# nzxt-gamma-usb3.net
KiCad netlist of a schematic drawn in EAGLE
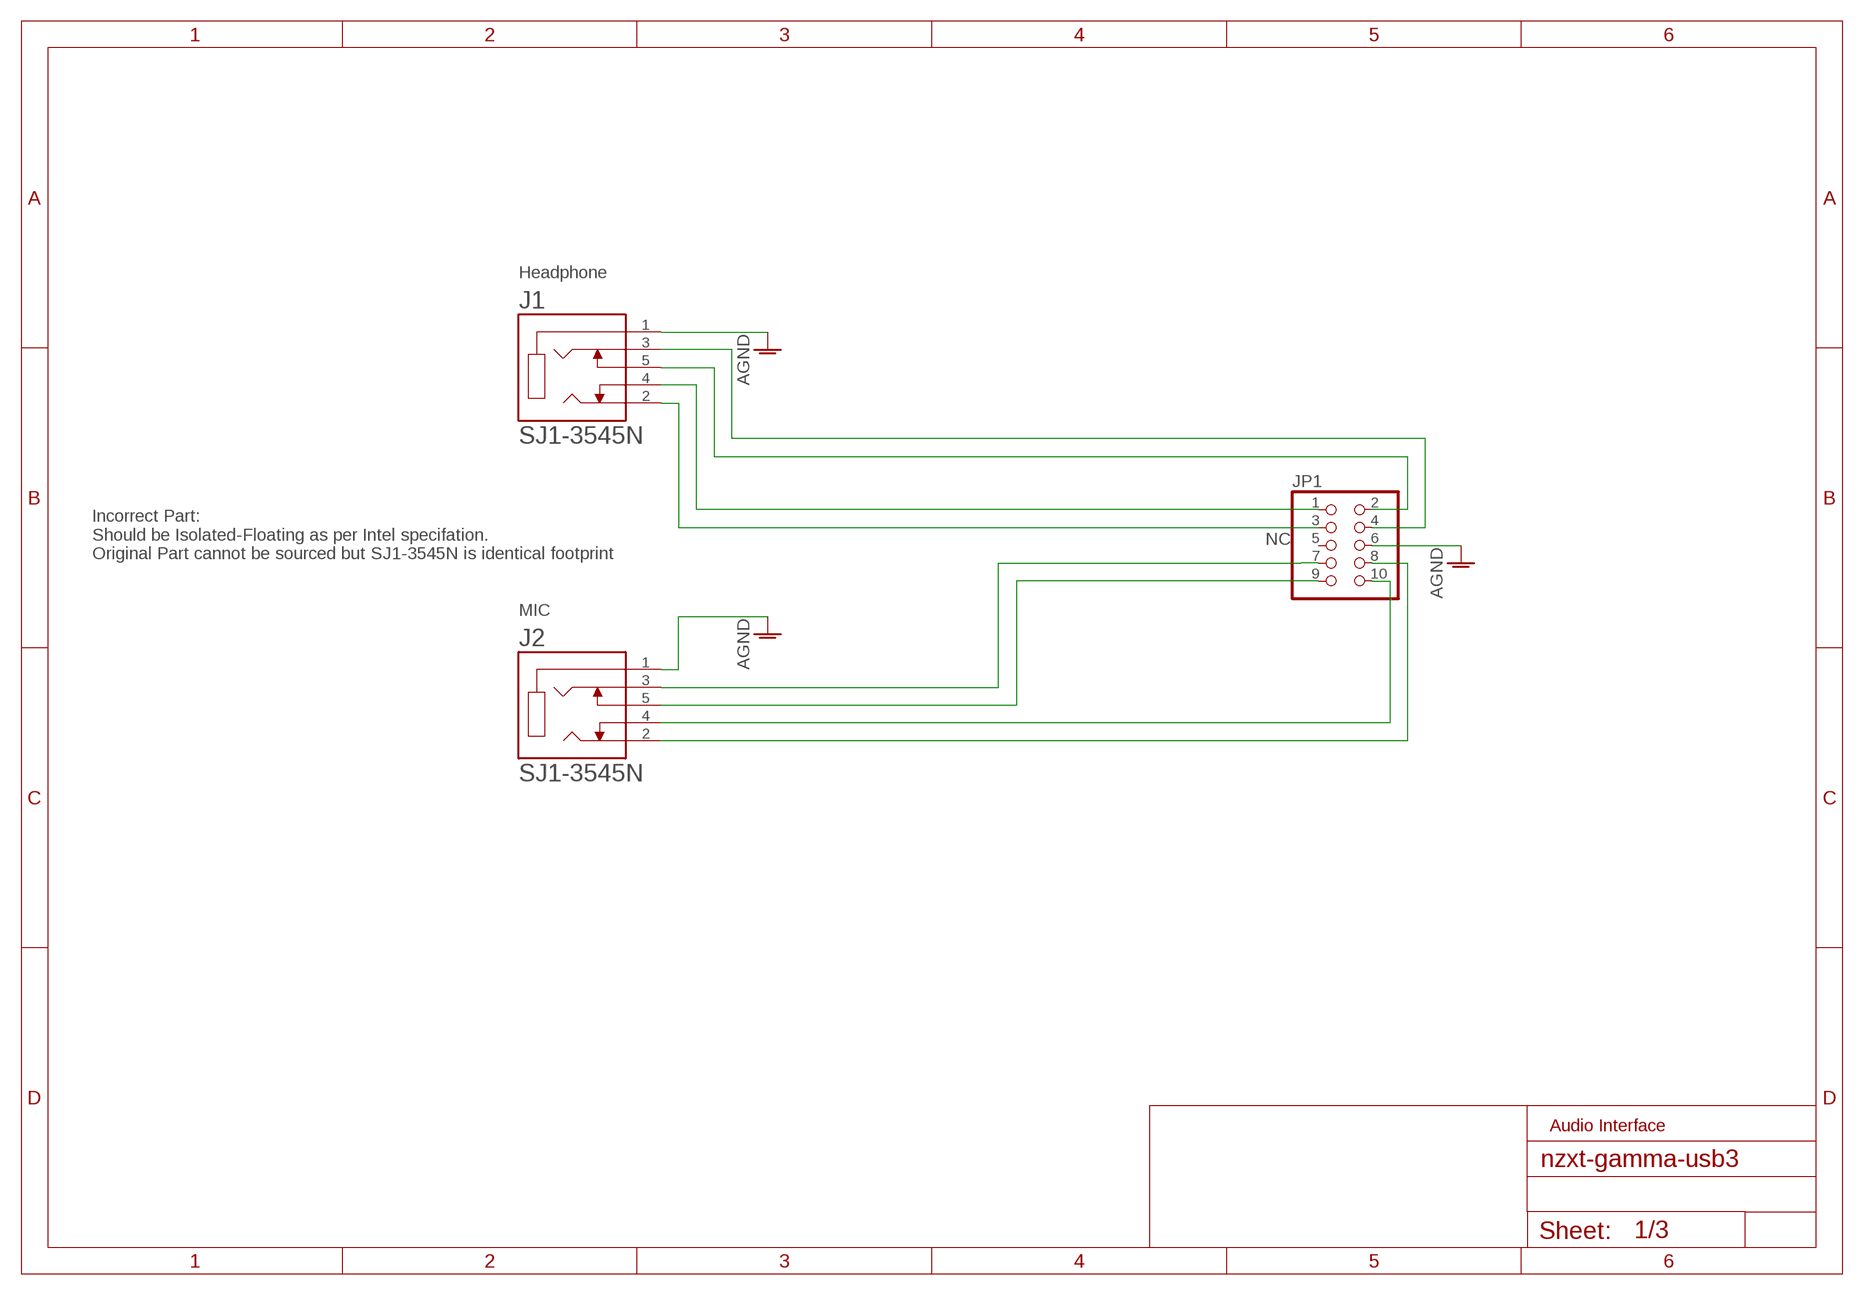
[diagram p0: schematic, sheet 1]
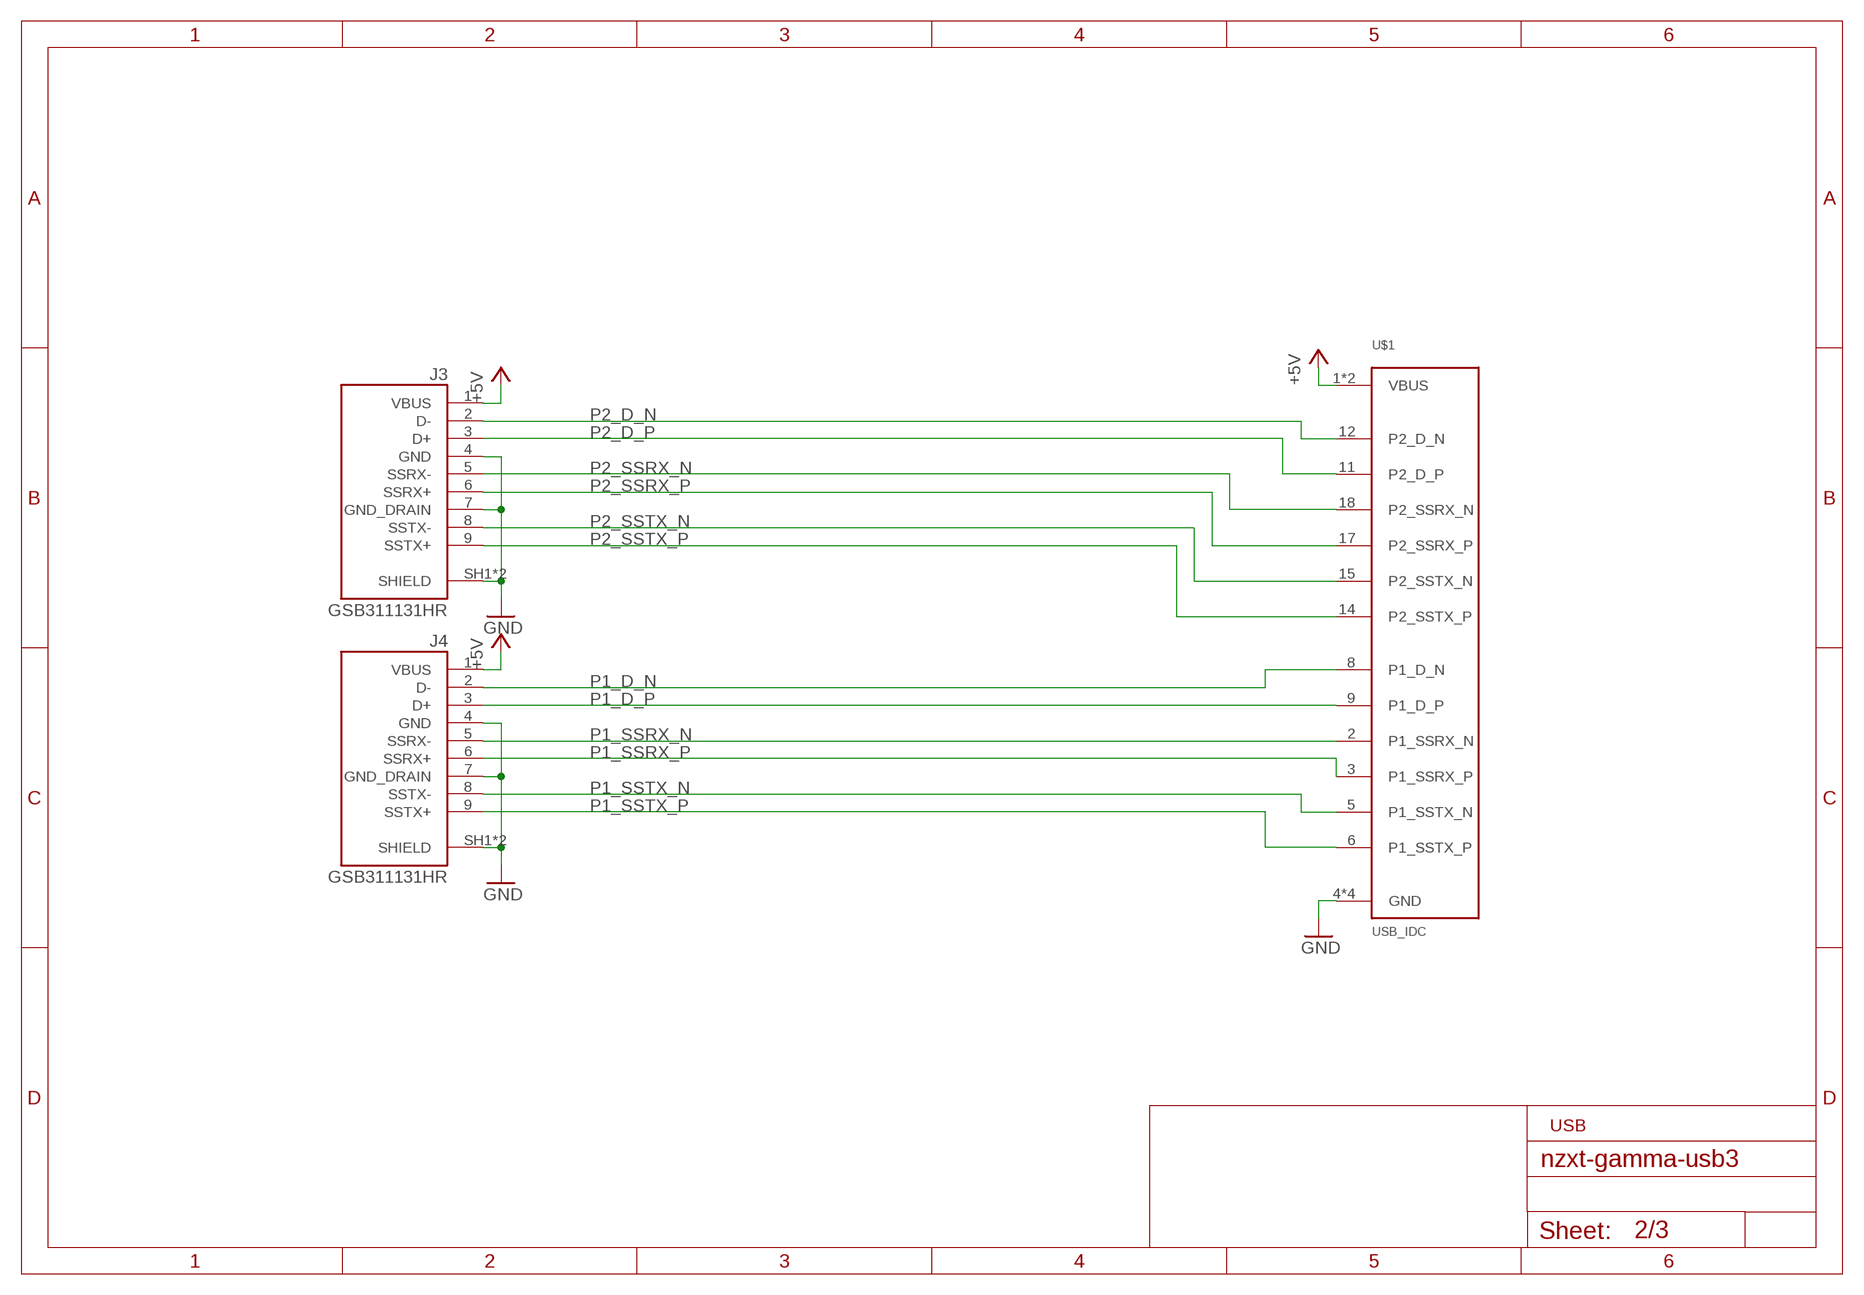
[diagram p1: schematic, sheet 2]
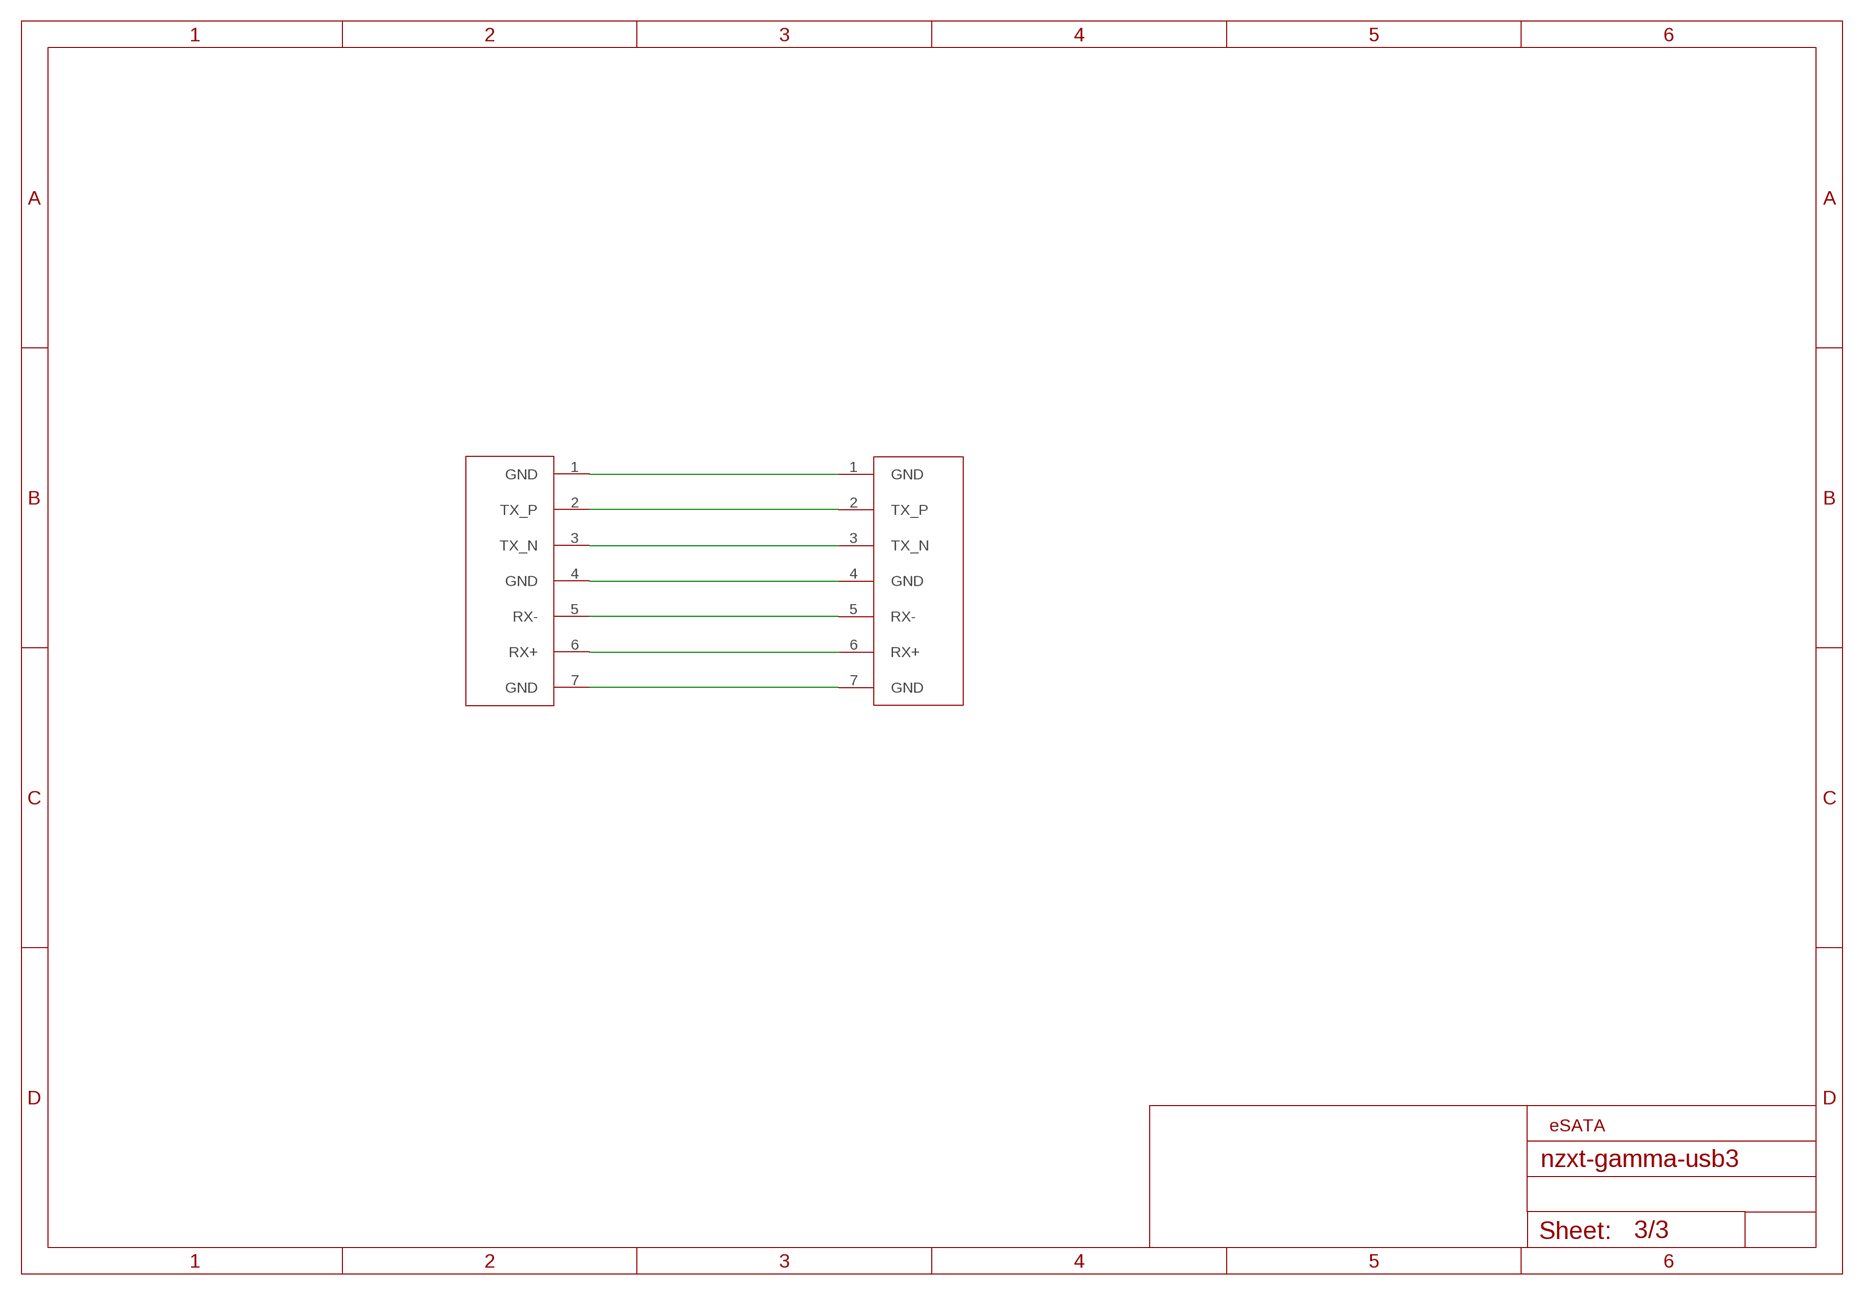
[diagram p2: schematic, sheet 3]

(export (version "E")
  (design (tool "Eeschema 10.0.6"))
  (components
    (comp (ref "J3")
      (value "GSB311131HR")
      (footprint "eagle-import:AMPHENOL_GSB311131HR")
      (fields (field (name "MF") "Amphenol Commercial"))
      (libsource (lib "eagle-import") (part "GSB311131HR"))
    )
    (comp (ref "J4")
      (value "GSB311131HR")
      (footprint "eagle-import:AMPHENOL_GSB311131HR")
      (fields (field (name "MF") "Amphenol Commercial"))
      (libsource (lib "eagle-import") (part "GSB311131HR"))
    )
    (comp (ref "U$1")
      (value "USB_IDC")
      (footprint "eagle-import:USB3_IDC")
      (libsource (lib "eagle-import") (part "USB_IDC"))
    )
    (comp (ref "U$2")
      (value "G091208300LF")
      (footprint "eagle-import:G091208300LF")
      (libsource (lib "eagle-import") (part "G091208300LF"))
    )
    (comp (ref "U$3")
      (value "0678007001")
      (footprint "eagle-import:0678007001")
      (fields (field (name "MF") "Molex"))
      (libsource (lib "eagle-import") (part "0678007001"))
    )
    (comp (ref "J1")
      (value "SJ1-3545N")
      (footprint "eagle-import:CUI_SJ1-3545N")
      (fields (field (name "MANUFACTURER") "CUI"))
      (libsource (lib "eagle-import") (part "SJ1-3545N"))
    )
    (comp (ref "J2")
      (value "SJ1-3545N")
      (footprint "eagle-import:CUI_SJ1-3545N")
      (fields (field (name "MANUFACTURER") "CUI"))
      (libsource (lib "eagle-import") (part "SJ1-3545N"))
    )
    (comp (ref "JP1")
      (value "PINHD-2X5")
      (footprint "eagle-import:2X05")
      (libsource (lib "eagle-import") (part "PINHD-2X5"))
    )
  )
  (nets
    (net (code "1") (name "+5V") (class "Default")
      (node (ref "J3") (pin "1") (pinfunction "VBUS_1") (pintype "passive"))
      (node (ref "J4") (pin "1") (pinfunction "VBUS_1") (pintype "passive"))
      (node (ref "U$1") (pin "1") (pinfunction "VBUS_1") (pintype "bidirectional"))
      (node (ref "U$1") (pin "19") (pinfunction "VBUS_19") (pintype "bidirectional"))
    )
    (net (code "2") (name "AGND") (class "Default")
      (node (ref "J1") (pin "1") (pinfunction "1_1") (pintype "passive"))
      (node (ref "J2") (pin "1") (pinfunction "1_1") (pintype "passive"))
      (node (ref "JP1") (pin "6") (pinfunction "6_6") (pintype "passive"))
    )
    (net (code "3") (name "GND") (class "Default")
      (node (ref "J3") (pin "4") (pinfunction "GND_4") (pintype "passive"))
      (node (ref "J3") (pin "7") (pinfunction "GND_DRAIN_7") (pintype "passive"))
      (node (ref "J3") (pin "SH1") (pinfunction "SHIELD_SH1") (pintype "passive"))
      (node (ref "J3") (pin "SH2") (pinfunction "SHIELD_SH2") (pintype "passive"))
      (node (ref "J4") (pin "4") (pinfunction "GND_4") (pintype "passive"))
      (node (ref "J4") (pin "7") (pinfunction "GND_DRAIN_7") (pintype "passive"))
      (node (ref "J4") (pin "SH1") (pinfunction "SHIELD_SH1") (pintype "passive"))
      (node (ref "J4") (pin "SH2") (pinfunction "SHIELD_SH2") (pintype "passive"))
      (node (ref "U$1") (pin "13") (pinfunction "GND_13") (pintype "bidirectional"))
      (node (ref "U$1") (pin "16") (pinfunction "GND_16") (pintype "bidirectional"))
      (node (ref "U$1") (pin "4") (pinfunction "GND_4") (pintype "bidirectional"))
      (node (ref "U$1") (pin "7") (pinfunction "GND_7") (pintype "bidirectional"))
    )
    (net (code "4") (name "Net-(J1-Pad2)") (class "Default")
      (node (ref "J1") (pin "2") (pinfunction "2_2") (pintype "passive"))
      (node (ref "JP1") (pin "3") (pinfunction "3_3") (pintype "passive"))
    )
    (net (code "5") (name "Net-(J1-Pad3)") (class "Default")
      (node (ref "J1") (pin "3") (pinfunction "3_3") (pintype "passive"))
      (node (ref "JP1") (pin "4") (pinfunction "4_4") (pintype "passive"))
    )
    (net (code "6") (name "Net-(J1-Pad4)") (class "Default")
      (node (ref "J1") (pin "4") (pinfunction "4_4") (pintype "passive"))
      (node (ref "JP1") (pin "1") (pinfunction "1_1") (pintype "passive"))
    )
    (net (code "7") (name "Net-(J1-Pad5)") (class "Default")
      (node (ref "J1") (pin "5") (pinfunction "5_5") (pintype "passive"))
      (node (ref "JP1") (pin "2") (pinfunction "2_2") (pintype "passive"))
    )
    (net (code "8") (name "Net-(J2-Pad2)") (class "Default")
      (node (ref "J2") (pin "2") (pinfunction "2_2") (pintype "passive"))
      (node (ref "JP1") (pin "8") (pinfunction "8_8") (pintype "passive"))
    )
    (net (code "9") (name "Net-(J2-Pad3)") (class "Default")
      (node (ref "J2") (pin "3") (pinfunction "3_3") (pintype "passive"))
      (node (ref "JP1") (pin "7") (pinfunction "7_7") (pintype "passive"))
    )
    (net (code "10") (name "Net-(J2-Pad4)") (class "Default")
      (node (ref "J2") (pin "4") (pinfunction "4_4") (pintype "passive"))
      (node (ref "JP1") (pin "10") (pinfunction "10_10") (pintype "passive"))
    )
    (net (code "11") (name "Net-(J2-Pad5)") (class "Default")
      (node (ref "J2") (pin "5") (pinfunction "5_5") (pintype "passive"))
      (node (ref "JP1") (pin "9") (pinfunction "9_9") (pintype "passive"))
    )
    (net (code "12") (name "Net-(U$2-GND-Pad1)") (class "Default")
      (node (ref "U$2") (pin "1") (pinfunction "GND_1") (pintype "bidirectional"))
      (node (ref "U$3") (pin "1") (pinfunction "GND_1") (pintype "bidirectional"))
    )
    (net (code "13") (name "Net-(U$2-GND-Pad4)") (class "Default")
      (node (ref "U$2") (pin "4") (pinfunction "GND_4") (pintype "bidirectional"))
      (node (ref "U$3") (pin "4") (pinfunction "GND_4") (pintype "bidirectional"))
    )
    (net (code "14") (name "Net-(U$2-GND-Pad7)") (class "Default")
      (node (ref "U$2") (pin "7") (pinfunction "GND_7") (pintype "bidirectional"))
      (node (ref "U$3") (pin "7") (pinfunction "GND_7") (pintype "bidirectional"))
    )
    (net (code "15") (name "Net-(U$2-RX+)") (class "Default")
      (node (ref "U$2") (pin "6") (pinfunction "RX+_6") (pintype "bidirectional"))
      (node (ref "U$3") (pin "6") (pinfunction "RX+_6") (pintype "bidirectional"))
    )
    (net (code "16") (name "Net-(U$2-RX-)") (class "Default")
      (node (ref "U$2") (pin "5") (pinfunction "RX-_5") (pintype "bidirectional"))
      (node (ref "U$3") (pin "5") (pinfunction "RX-_5") (pintype "bidirectional"))
    )
    (net (code "17") (name "Net-(U$2-TX_N)") (class "Default")
      (node (ref "U$2") (pin "3") (pinfunction "TX_N_3") (pintype "bidirectional"))
      (node (ref "U$3") (pin "3") (pinfunction "TX_N_3") (pintype "bidirectional"))
    )
    (net (code "18") (name "Net-(U$2-TX_P)") (class "Default")
      (node (ref "U$2") (pin "2") (pinfunction "TX_P_2") (pintype "bidirectional"))
      (node (ref "U$3") (pin "2") (pinfunction "TX_P_2") (pintype "bidirectional"))
    )
    (net (code "19") (name "P1_D_N") (class "Default")
      (node (ref "J4") (pin "2") (pinfunction "D-_2") (pintype "passive"))
      (node (ref "U$1") (pin "8") (pinfunction "P1_D_N_8") (pintype "bidirectional"))
    )
    (net (code "20") (name "P1_D_P") (class "Default")
      (node (ref "J4") (pin "3") (pinfunction "D+_3") (pintype "passive"))
      (node (ref "U$1") (pin "9") (pinfunction "P1_D_P_9") (pintype "bidirectional"))
    )
    (net (code "21") (name "P1_SSRX_N") (class "Default")
      (node (ref "J4") (pin "5") (pinfunction "SSRX-_5") (pintype "passive"))
      (node (ref "U$1") (pin "2") (pinfunction "P1_SSRX_N_2") (pintype "bidirectional"))
    )
    (net (code "22") (name "P1_SSRX_P") (class "Default")
      (node (ref "J4") (pin "6") (pinfunction "SSRX+_6") (pintype "passive"))
      (node (ref "U$1") (pin "3") (pinfunction "P1_SSRX_P_3") (pintype "bidirectional"))
    )
    (net (code "23") (name "P1_SSTX_N") (class "Default")
      (node (ref "J4") (pin "8") (pinfunction "SSTX-_8") (pintype "passive"))
      (node (ref "U$1") (pin "5") (pinfunction "P1_SSTX_N_5") (pintype "bidirectional"))
    )
    (net (code "24") (name "P1_SSTX_P") (class "Default")
      (node (ref "J4") (pin "9") (pinfunction "SSTX+_9") (pintype "passive"))
      (node (ref "U$1") (pin "6") (pinfunction "P1_SSTX_P_6") (pintype "bidirectional"))
    )
    (net (code "25") (name "P2_D_N") (class "Default")
      (node (ref "J3") (pin "2") (pinfunction "D-_2") (pintype "passive"))
      (node (ref "U$1") (pin "12") (pinfunction "P2_D_N_12") (pintype "bidirectional"))
    )
    (net (code "26") (name "P2_D_P") (class "Default")
      (node (ref "J3") (pin "3") (pinfunction "D+_3") (pintype "passive"))
      (node (ref "U$1") (pin "11") (pinfunction "P2_D_P_11") (pintype "bidirectional"))
    )
    (net (code "27") (name "P2_SSRX_N") (class "Default")
      (node (ref "J3") (pin "5") (pinfunction "SSRX-_5") (pintype "passive"))
      (node (ref "U$1") (pin "18") (pinfunction "P2_SSRX_N_18") (pintype "bidirectional"))
    )
    (net (code "28") (name "P2_SSRX_P") (class "Default")
      (node (ref "J3") (pin "6") (pinfunction "SSRX+_6") (pintype "passive"))
      (node (ref "U$1") (pin "17") (pinfunction "P2_SSRX_P_17") (pintype "bidirectional"))
    )
    (net (code "29") (name "P2_SSTX_N") (class "Default")
      (node (ref "J3") (pin "8") (pinfunction "SSTX-_8") (pintype "passive"))
      (node (ref "U$1") (pin "15") (pinfunction "P2_SSTX_N_15") (pintype "bidirectional"))
    )
    (net (code "30") (name "P2_SSTX_P") (class "Default")
      (node (ref "J3") (pin "9") (pinfunction "SSTX+_9") (pintype "passive"))
      (node (ref "U$1") (pin "14") (pinfunction "P2_SSTX_P_14") (pintype "bidirectional"))
    )
    (net (code "31") (name "unconnected-(JP1-Pad5)") (class "Default")
      (node (ref "JP1") (pin "5") (pinfunction "5_5") (pintype "passive"))
    )
  )
)
